# DIOT_PSU_AC_180.net
KiCad netlist of a schematic drawn in Altium Designer
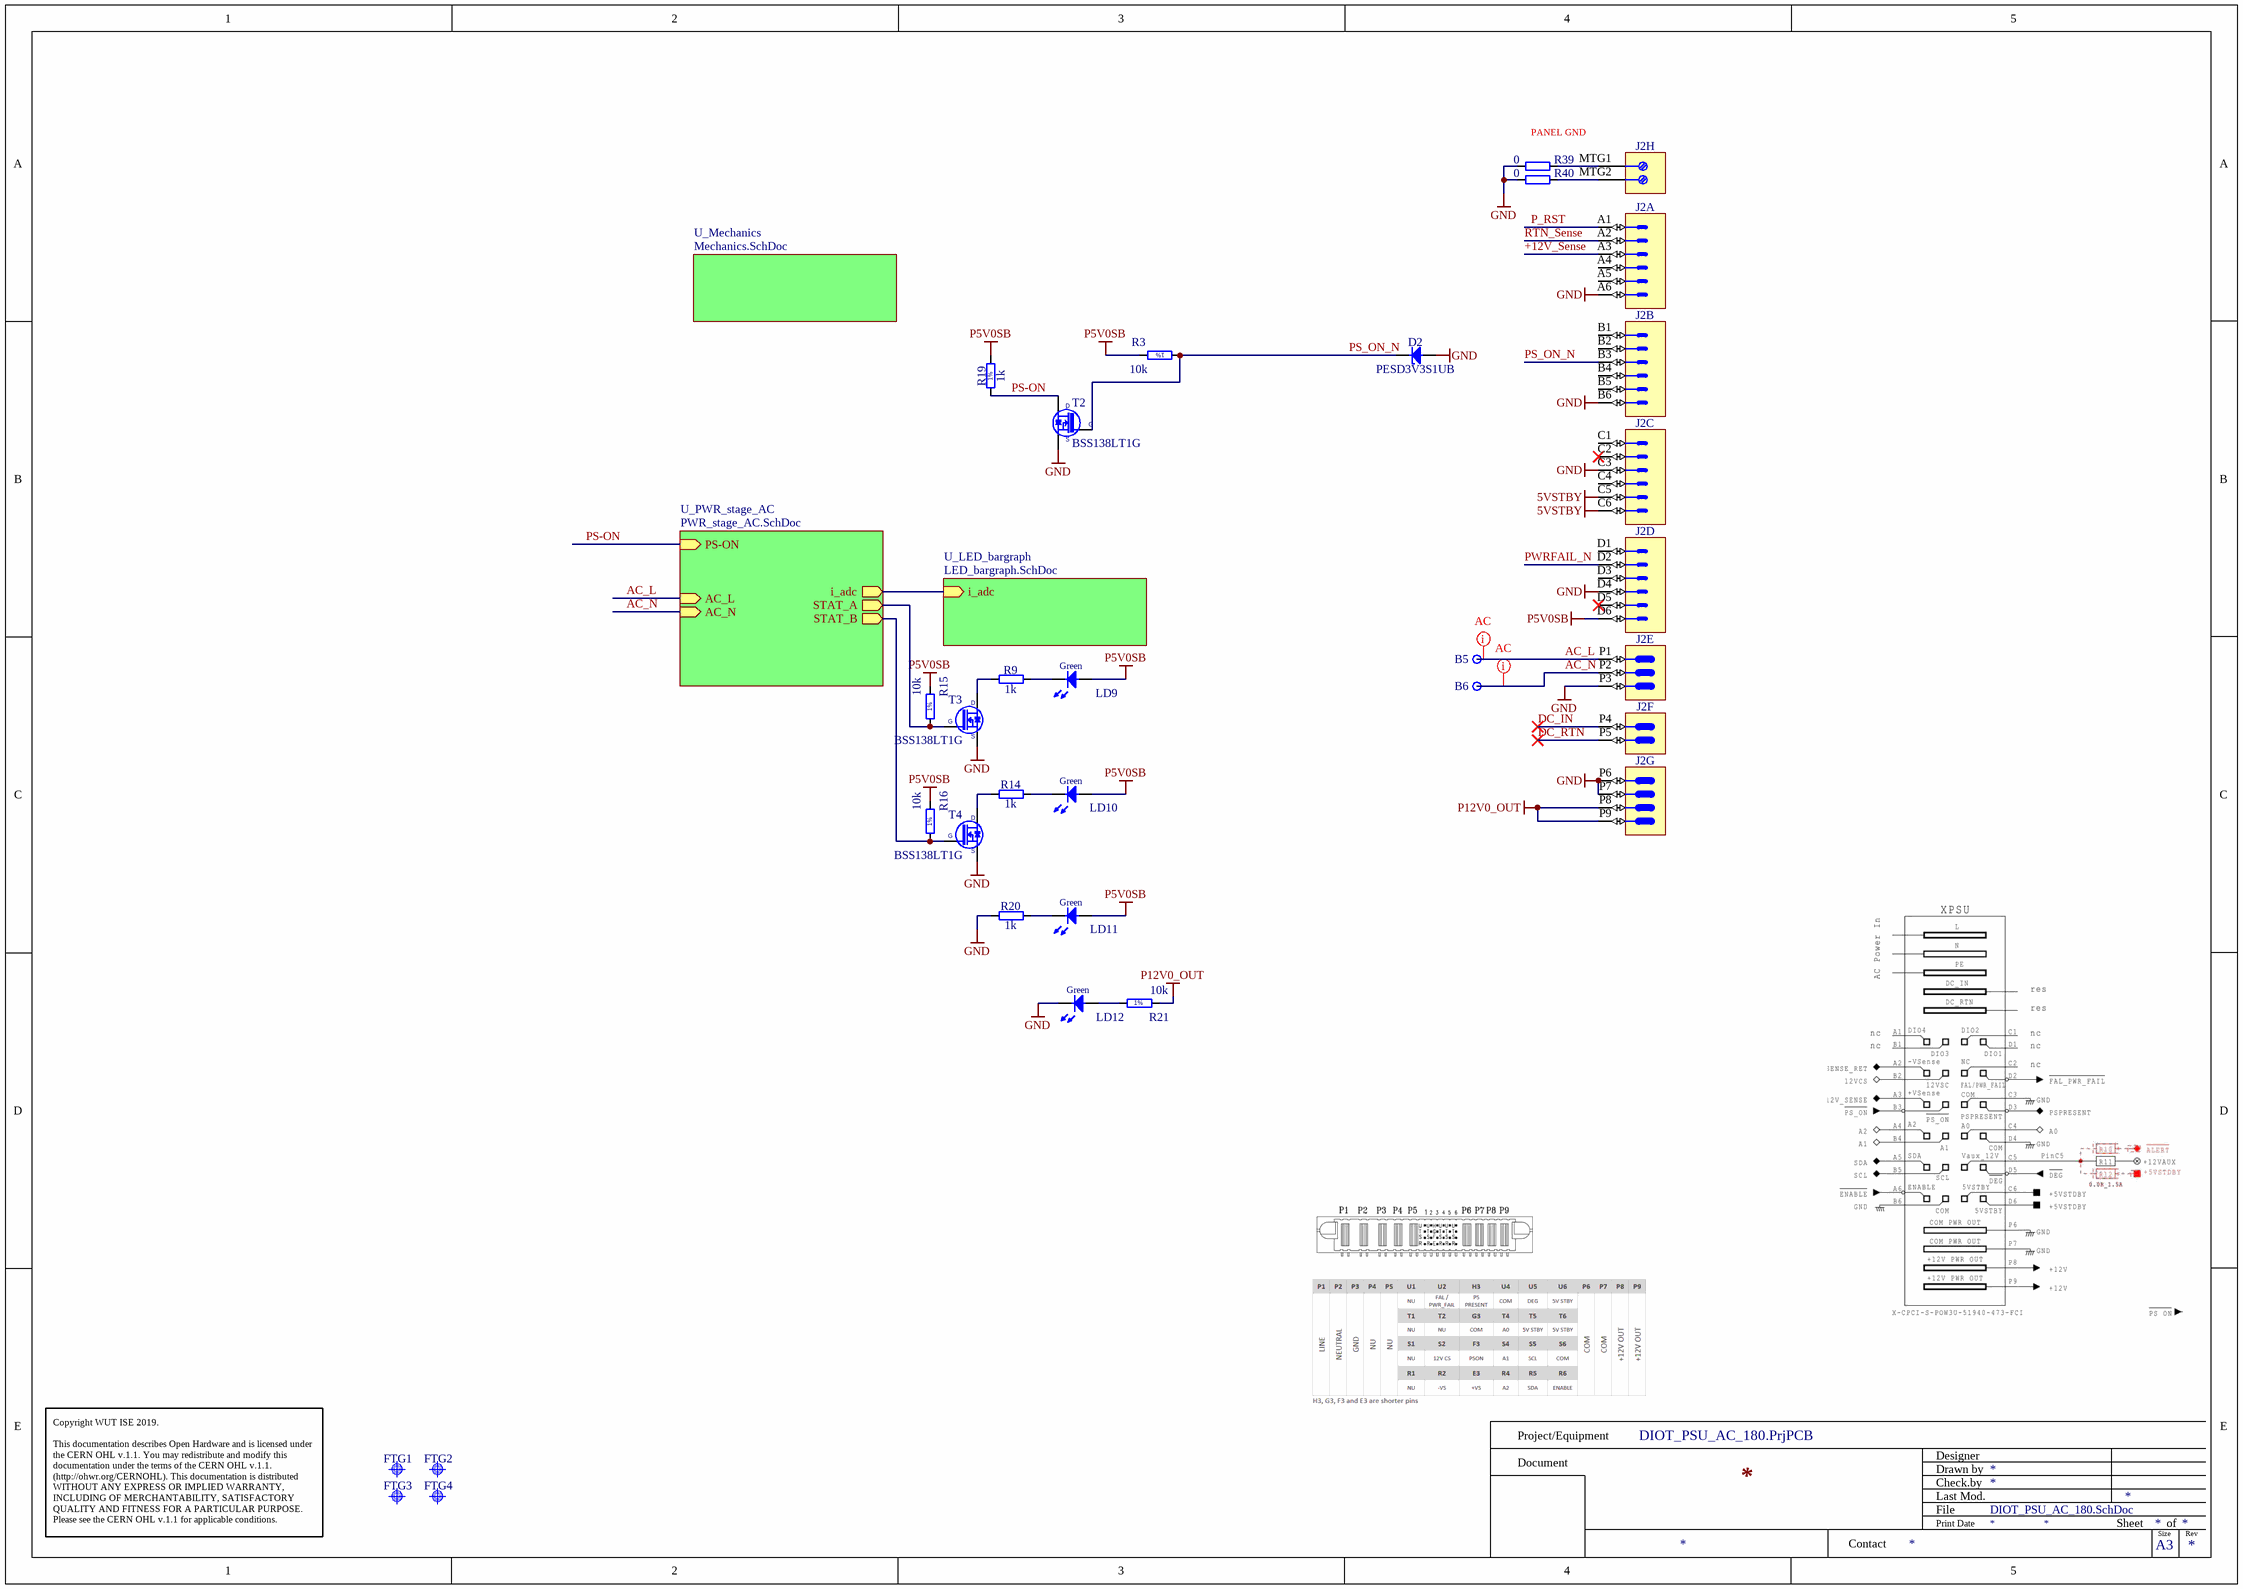
[diagram p0: DIOT_PSU_AC_180.SchDoc]

(export (version "E")
  (design (tool "Eeschema 10.0.6"))
  (components
    (comp (ref "B5")
      (value "Plated Hole")
      (footprint "c220h150")
      (description "Single Terminal Socket")
      (fields (field (name "PART NUMBER") "PLATED_HOLE1.5_PAD2.2") (field (name "AUTHOR") "CERN DEM JLC"))
      (libsource (lib "Eletro-mechanical") (part "Single Terminal Socket"))
    )
    (comp (ref "B6")
      (value "Plated Hole")
      (footprint "c220h150")
      (description "Single Terminal Socket")
      (fields (field (name "PART NUMBER") "PLATED_HOLE1.5_PAD2.2") (field (name "AUTHOR") "CERN DEM JLC"))
      (libsource (lib "Eletro-mechanical") (part "Single Terminal Socket"))
    )
    (comp (ref "D2")
      (value "PESD3V3S1UB")
      (footprint "SODFL1608X65N")
      (description "ESD protection diode")
      (fields
        (field (name "VOLTAGE") "3V3")
        (field (name "POWER") "330W")
        (field (name "AUTHOR") "CERN DEM JLC")
      )
      (libsource (lib "ICs And Semiconductors") (part "Diode ESD"))
    )
    (comp (ref "FTG1")
      (value "Use only in PCB")
      (footprint "FIDUCIAL_TOP_C100-200")
      (description "Fiducial Target")
      (fields (field (name "PART NUMBER") "FIDUCIAL_TARGET_C100-200") (field (name "AUTHOR") "CERN DEM JLC"))
      (libsource (lib "Eletro-mechanical") (part "Fiducial Target"))
    )
    (comp (ref "FTG2")
      (value "Use only in PCB")
      (footprint "FIDUCIAL_TOP_S100-200")
      (description "Fiducial Target")
      (fields (field (name "PART NUMBER") "FIDUCIAL_TARGET_S100-200") (field (name "AUTHOR") "CERN DEM JLC"))
      (libsource (lib "Eletro-mechanical") (part "Fiducial Target"))
    )
    (comp (ref "FTG3")
      (value "Use only in PCB")
      (footprint "FIDUCIAL_TOP_C100-200")
      (description "Fiducial Target")
      (fields (field (name "PART NUMBER") "FIDUCIAL_TARGET_C100-200") (field (name "AUTHOR") "CERN DEM JLC"))
      (libsource (lib "Eletro-mechanical") (part "Fiducial Target"))
    )
    (comp (ref "FTG4")
      (value "Use only in PCB")
      (footprint "FIDUCIAL_TOP_S100-200")
      (description "Fiducial Target")
      (fields (field (name "PART NUMBER") "FIDUCIAL_TARGET_S100-200") (field (name "AUTHOR") "CERN DEM JLC"))
      (libsource (lib "Eletro-mechanical") (part "Fiducial Target"))
    )
    (comp (ref "J2")
      (value "PwrBlade")
      (footprint "AMPHENOL_51939-667")
      (description "Thru-Hole, Lead 3.43mm, PowerBlade Right Angled Power Connector 3ACP 2P 24S 4P Contacts")
      (fields
        (field (name "PART NUMBER") "AMPHENOL_51939-667")
        (field (name "MANUFACTURER") "AMPHENOL")
        (field (name "AUTHOR") "CERN DEM JLC")
      )
      (libsource (lib "Connectors") (part "AMPHENOL_51939-667"))
    )
    (comp (ref "LD9")
      (value "Green")
      (footprint "LED_AVAGO_HSME-C120")
      (description "LED Green 1C 2A")
      (fields
        (field (name "PART NUMBER") "LED_AVAGO_HSME-C120")
        (field (name "MANUFACTURER") "AVAGO TECHNOLOGIES")
        (field (name "AUTHOR") "CERN DEM JMW")
      )
      (libsource (lib "ICs And Semiconductors") (part "LED Green 1C 2A"))
    )
    (comp (ref "LD10")
      (value "Green")
      (footprint "LED_AVAGO_HSME-C120")
      (description "LED Green 1C 2A")
      (fields
        (field (name "PART NUMBER") "LED_AVAGO_HSME-C120")
        (field (name "MANUFACTURER") "AVAGO TECHNOLOGIES")
        (field (name "AUTHOR") "CERN DEM JMW")
      )
      (libsource (lib "ICs And Semiconductors") (part "LED Green 1C 2A"))
    )
    (comp (ref "LD11")
      (value "Green")
      (footprint "LED_AVAGO_HSME-C120")
      (description "LED Green 1C 2A")
      (fields
        (field (name "PART NUMBER") "LED_AVAGO_HSME-C120")
        (field (name "MANUFACTURER") "AVAGO TECHNOLOGIES")
        (field (name "AUTHOR") "CERN DEM JMW")
      )
      (libsource (lib "ICs And Semiconductors") (part "LED Green 1C 2A"))
    )
    (comp (ref "LD12")
      (value "Green")
      (footprint "LED_AVAGO_HSME-C120")
      (description "LED Green 1C 2A")
      (fields
        (field (name "PART NUMBER") "LED_AVAGO_HSME-C120")
        (field (name "MANUFACTURER") "AVAGO TECHNOLOGIES")
        (field (name "AUTHOR") "CERN DEM JMW")
      )
      (libsource (lib "ICs And Semiconductors") (part "LED Green 1C 2A"))
    )
    (comp (ref "R3")
      (value "10k")
      (footprint "RESC1005X40N")
      (description "Resistor - 1%")
      (fields
        (field (name "PART NUMBER") "R0402_10K_1%_0.0625W_100PPM")
        (field (name "POWER") "0.0625W")
        (field (name "AUTHOR") "CERN DEM JLC")
      )
      (libsource (lib "") (part "Resistor - 1%_1"))
    )
    (comp (ref "R9")
      (value "1k")
      (footprint "RESC1608X55N")
      (description "Resistor - 1%")
      (fields
        (field (name "PART NUMBER") "R0603_1K_1%_0.1W_100PPM")
        (field (name "POWER") "0.1W")
        (field (name "AUTHOR") "CERN DEM JLC")
      )
      (libsource (lib "Resistors") (part "Resistor - 1%"))
    )
    (comp (ref "R14")
      (value "1k")
      (footprint "RESC1608X55N")
      (description "Resistor - 1%")
      (fields
        (field (name "PART NUMBER") "R0603_1K_1%_0.1W_100PPM")
        (field (name "POWER") "0.1W")
        (field (name "AUTHOR") "CERN DEM JLC")
      )
      (libsource (lib "Resistors") (part "Resistor - 1%"))
    )
    (comp (ref "R15")
      (value "10k")
      (footprint "RESC1005X40N")
      (description "Resistor - 1%")
      (fields
        (field (name "PART NUMBER") "R0402_10K_1%_0.0625W_100PPM")
        (field (name "POWER") "0.0625W")
        (field (name "AUTHOR") "CERN DEM JLC")
      )
      (libsource (lib "") (part "Resistor - 1%_1"))
    )
    (comp (ref "R16")
      (value "10k")
      (footprint "RESC1005X40N")
      (description "Resistor - 1%")
      (fields
        (field (name "PART NUMBER") "R0402_10K_1%_0.0625W_100PPM")
        (field (name "POWER") "0.0625W")
        (field (name "AUTHOR") "CERN DEM JLC")
      )
      (libsource (lib "") (part "Resistor - 1%_1"))
    )
    (comp (ref "R19")
      (value "1k")
      (footprint "RESC1005X40N")
      (description "Resistor - 1%")
      (fields
        (field (name "PART NUMBER") "R0402_1K_1%_0.0625W_100PPM")
        (field (name "POWER") "0.0625W")
        (field (name "AUTHOR") "CERN DEM JLC")
      )
      (libsource (lib "") (part "Resistor - 1%_1"))
    )
    (comp (ref "R20")
      (value "1k")
      (footprint "RESC1608X55N")
      (description "Resistor - 1%")
      (fields
        (field (name "PART NUMBER") "R0603_1K_1%_0.1W_100PPM")
        (field (name "POWER") "0.1W")
        (field (name "AUTHOR") "CERN DEM JLC")
      )
      (libsource (lib "Resistors") (part "Resistor - 1%"))
    )
    (comp (ref "R21")
      (value "10k")
      (footprint "RESC1005X40N")
      (description "Resistor - 1%")
      (fields
        (field (name "PART NUMBER") "R0402_10K_1%_0.0625W_100PPM")
        (field (name "POWER") "0.0625W")
        (field (name "AUTHOR") "CERN DEM JLC")
      )
      (libsource (lib "") (part "Resistor - 1%_1"))
    )
    (comp (ref "R39")
      (value "0")
      (footprint "RESC1608X55N")
      (description "Resistor")
      (fields
        (field (name "PART NUMBER") "R0603_0R_JUMPER")
        (field (name "MANUFACTURER") "GENERIC")
        (field (name "AUTHOR") "CERN DEM JLC")
      )
      (libsource (lib "Resistors") (part "Resistor"))
    )
    (comp (ref "R40")
      (value "0")
      (footprint "RESC1608X55N")
      (description "Resistor")
      (fields
        (field (name "PART NUMBER") "R0603_0R_JUMPER")
        (field (name "MANUFACTURER") "GENERIC")
        (field (name "AUTHOR") "CERN DEM JLC")
      )
      (libsource (lib "Resistors") (part "Resistor"))
    )
    (comp (ref "T2")
      (value "BSS138LT1G")
      (footprint "SOT95P240X110-3N")
      (description "N-CHANNEL MOSFET WITH DIODE")
      (fields (field (name "MANUFACTURER") "ON SEMICONDUCTOR") (field (name "AUTHOR") "CERN DEM JLC"))
      (libsource (lib "ICs And Semiconductors") (part "N-MOSFET-D 1G 2S 3D"))
    )
    (comp (ref "T3")
      (value "BSS138LT1G")
      (footprint "SOT95P240X110-3N")
      (description "N-CHANNEL MOSFET WITH DIODE")
      (fields (field (name "MANUFACTURER") "ON SEMICONDUCTOR") (field (name "AUTHOR") "CERN DEM JLC"))
      (libsource (lib "") (part "N-MOSFET-D 1G 2S 3D_1"))
    )
    (comp (ref "T4")
      (value "BSS138LT1G")
      (footprint "SOT95P240X110-3N")
      (description "N-CHANNEL MOSFET WITH DIODE")
      (fields (field (name "MANUFACTURER") "ON SEMICONDUCTOR") (field (name "AUTHOR") "CERN DEM JLC"))
      (libsource (lib "") (part "N-MOSFET-D 1G 2S 3D_1"))
    )
  )
  (nets
    (net (code "1") (name "/+12V_Sense") (class "Default")
      (node (ref "J2") (pin "A3") (pinfunction "A3_A3") (pintype "bidirectional"))
    )
    (net (code "2") (name "/AC_L") (class "Default")
      (node (ref "B5") (pin "1") (pinfunction "1_1") (pintype "bidirectional"))
      (node (ref "J2") (pin "P1") (pinfunction "P1_P1") (pintype "bidirectional"))
    )
    (net (code "3") (name "/AC_N") (class "Default")
      (node (ref "B6") (pin "1") (pinfunction "1_1") (pintype "bidirectional"))
      (node (ref "J2") (pin "P2") (pinfunction "P2_P2") (pintype "bidirectional"))
    )
    (net (code "4") (name "/DC_IN") (class "Default")
      (node (ref "J2") (pin "P4") (pinfunction "P4_P4") (pintype "bidirectional+no_connect"))
    )
    (net (code "5") (name "/DC_RTN") (class "Default")
      (node (ref "J2") (pin "P5") (pinfunction "P5_P5") (pintype "bidirectional+no_connect"))
    )
    (net (code "6") (name "/PS-ON") (class "Default")
      (node (ref "R19") (pin "1") (pinfunction "1_1") (pintype "passive"))
      (node (ref "T2") (pin "3") (pinfunction "D_3") (pintype "passive"))
    )
    (net (code "7") (name "/PS_ON_N") (class "Default")
      (node (ref "D2") (pin "1") (pinfunction "C_1") (pintype "passive"))
      (node (ref "J2") (pin "B3") (pinfunction "B3_B3") (pintype "bidirectional"))
      (node (ref "R3") (pin "1") (pinfunction "1_1") (pintype "passive"))
      (node (ref "T2") (pin "1") (pinfunction "G_1") (pintype "passive"))
    )
    (net (code "8") (name "/PWRFAIL_N") (class "Default")
      (node (ref "J2") (pin "D2") (pinfunction "D2_D2") (pintype "bidirectional"))
    )
    (net (code "9") (name "/P_RST") (class "Default")
      (node (ref "J2") (pin "A1") (pinfunction "A1_A1") (pintype "bidirectional"))
    )
    (net (code "10") (name "/RTN_Sense") (class "Default")
      (node (ref "J2") (pin "A2") (pinfunction "A2_A2") (pintype "bidirectional"))
    )
    (net (code "11") (name "/STAT_A") (class "Default")
      (node (ref "R15") (pin "1") (pinfunction "1_1") (pintype "passive"))
      (node (ref "T3") (pin "1") (pinfunction "G_1") (pintype "passive"))
    )
    (net (code "12") (name "/STAT_B") (class "Default")
      (node (ref "R16") (pin "1") (pinfunction "1_1") (pintype "passive"))
      (node (ref "T4") (pin "1") (pinfunction "G_1") (pintype "passive"))
    )
    (net (code "14") (name "5VSTBY") (class "Default")
      (node (ref "J2") (pin "C5") (pinfunction "C5_C5") (pintype "bidirectional"))
      (node (ref "J2") (pin "C6") (pinfunction "C6_C6") (pintype "bidirectional"))
    )
    (net (code "15") (name "GND") (class "Default")
      (node (ref "D2") (pin "2") (pinfunction "A_2") (pintype "passive"))
      (node (ref "J2") (pin "A6") (pinfunction "A6_A6") (pintype "bidirectional"))
      (node (ref "J2") (pin "B6") (pinfunction "B6_B6") (pintype "bidirectional"))
      (node (ref "J2") (pin "C3") (pinfunction "C3_C3") (pintype "bidirectional"))
      (node (ref "J2") (pin "D4") (pinfunction "D4_D4") (pintype "bidirectional"))
      (node (ref "J2") (pin "P3") (pinfunction "P3_P3") (pintype "bidirectional"))
      (node (ref "J2") (pin "P6") (pinfunction "P6_P6") (pintype "bidirectional"))
      (node (ref "J2") (pin "P7") (pinfunction "P7_P7") (pintype "bidirectional"))
      (node (ref "LD12") (pin "1") (pinfunction "C_1") (pintype "passive"))
      (node (ref "R20") (pin "1") (pinfunction "1_1") (pintype "passive"))
      (node (ref "R39") (pin "2") (pinfunction "2_2") (pintype "passive"))
      (node (ref "R40") (pin "2") (pinfunction "2_2") (pintype "passive"))
      (node (ref "T2") (pin "2") (pinfunction "S_2") (pintype "passive"))
      (node (ref "T3") (pin "2") (pinfunction "S_2") (pintype "passive"))
      (node (ref "T4") (pin "2") (pinfunction "S_2") (pintype "passive"))
    )
    (net (code "16") (name "Net-(J2-PadMTG1)") (class "Default")
      (node (ref "J2") (pin "MTG1") (pinfunction "MTG1_MTG1") (pintype "passive"))
      (node (ref "R39") (pin "1") (pinfunction "1_1") (pintype "passive"))
    )
    (net (code "17") (name "Net-(J2-PadMTG2)") (class "Default")
      (node (ref "J2") (pin "MTG2") (pinfunction "MTG2_MTG2") (pintype "passive"))
      (node (ref "R40") (pin "1") (pinfunction "1_1") (pintype "passive"))
    )
    (net (code "18") (name "Net-(LD9-C)") (class "Default")
      (node (ref "LD9") (pin "1") (pinfunction "C_1") (pintype "passive"))
      (node (ref "R9") (pin "2") (pinfunction "2_2") (pintype "passive"))
    )
    (net (code "19") (name "Net-(LD10-C)") (class "Default")
      (node (ref "LD10") (pin "1") (pinfunction "C_1") (pintype "passive"))
      (node (ref "R14") (pin "2") (pinfunction "2_2") (pintype "passive"))
    )
    (net (code "20") (name "Net-(LD11-C)") (class "Default")
      (node (ref "LD11") (pin "1") (pinfunction "C_1") (pintype "passive"))
      (node (ref "R20") (pin "2") (pinfunction "2_2") (pintype "passive"))
    )
    (net (code "21") (name "Net-(LD12-A)") (class "Default")
      (node (ref "LD12") (pin "2") (pinfunction "A_2") (pintype "passive"))
      (node (ref "R21") (pin "1") (pinfunction "1_1") (pintype "passive"))
    )
    (net (code "22") (name "Net-(T3-D)") (class "Default")
      (node (ref "R9") (pin "1") (pinfunction "1_1") (pintype "passive"))
      (node (ref "T3") (pin "3") (pinfunction "D_3") (pintype "passive"))
    )
    (net (code "23") (name "Net-(T4-D)") (class "Default")
      (node (ref "R14") (pin "1") (pinfunction "1_1") (pintype "passive"))
      (node (ref "T4") (pin "3") (pinfunction "D_3") (pintype "passive"))
    )
    (net (code "24") (name "P5V0SB") (class "Default")
      (node (ref "J2") (pin "D6") (pinfunction "D6_D6") (pintype "bidirectional"))
      (node (ref "LD10") (pin "2") (pinfunction "A_2") (pintype "passive"))
      (node (ref "LD11") (pin "2") (pinfunction "A_2") (pintype "passive"))
      (node (ref "LD9") (pin "2") (pinfunction "A_2") (pintype "passive"))
      (node (ref "R15") (pin "2") (pinfunction "2_2") (pintype "passive"))
      (node (ref "R16") (pin "2") (pinfunction "2_2") (pintype "passive"))
      (node (ref "R19") (pin "2") (pinfunction "2_2") (pintype "passive"))
      (node (ref "R3") (pin "2") (pinfunction "2_2") (pintype "passive"))
    )
    (net (code "25") (name "P12V0_OUT") (class "Default")
      (node (ref "J2") (pin "P8") (pinfunction "P8_P8") (pintype "bidirectional"))
      (node (ref "J2") (pin "P9") (pinfunction "P9_P9") (pintype "bidirectional"))
      (node (ref "R21") (pin "2") (pinfunction "2_2") (pintype "passive"))
    )
    (net (code "26") (name "unconnected-(J2-PadA4)") (class "Default")
      (node (ref "J2") (pin "A4") (pinfunction "A4_A4") (pintype "bidirectional"))
    )
    (net (code "27") (name "unconnected-(J2-PadA5)") (class "Default")
      (node (ref "J2") (pin "A5") (pinfunction "A5_A5") (pintype "bidirectional"))
    )
    (net (code "28") (name "unconnected-(J2-PadB1)") (class "Default")
      (node (ref "J2") (pin "B1") (pinfunction "B1_B1") (pintype "bidirectional"))
    )
    (net (code "29") (name "unconnected-(J2-PadB2)") (class "Default")
      (node (ref "J2") (pin "B2") (pinfunction "B2_B2") (pintype "bidirectional"))
    )
    (net (code "30") (name "unconnected-(J2-PadB4)") (class "Default")
      (node (ref "J2") (pin "B4") (pinfunction "B4_B4") (pintype "bidirectional"))
    )
    (net (code "31") (name "unconnected-(J2-PadB5)") (class "Default")
      (node (ref "J2") (pin "B5") (pinfunction "B5_B5") (pintype "bidirectional"))
    )
    (net (code "32") (name "unconnected-(J2-PadC1)") (class "Default")
      (node (ref "J2") (pin "C1") (pinfunction "C1_C1") (pintype "bidirectional"))
    )
    (net (code "33") (name "unconnected-(J2-PadC2)") (class "Default")
      (node (ref "J2") (pin "C2") (pinfunction "C2_C2") (pintype "bidirectional+no_connect"))
    )
    (net (code "34") (name "unconnected-(J2-PadC4)") (class "Default")
      (node (ref "J2") (pin "C4") (pinfunction "C4_C4") (pintype "bidirectional"))
    )
    (net (code "35") (name "unconnected-(J2-PadD1)") (class "Default")
      (node (ref "J2") (pin "D1") (pinfunction "D1_D1") (pintype "bidirectional"))
    )
    (net (code "36") (name "unconnected-(J2-PadD3)") (class "Default")
      (node (ref "J2") (pin "D3") (pinfunction "D3_D3") (pintype "bidirectional"))
    )
    (net (code "37") (name "unconnected-(J2-PadD5)") (class "Default")
      (node (ref "J2") (pin "D5") (pinfunction "D5_D5") (pintype "bidirectional+no_connect"))
    )
  )
)
